# 1-Schematic.net
KiCad netlist of a schematic drawn in EasyEDA
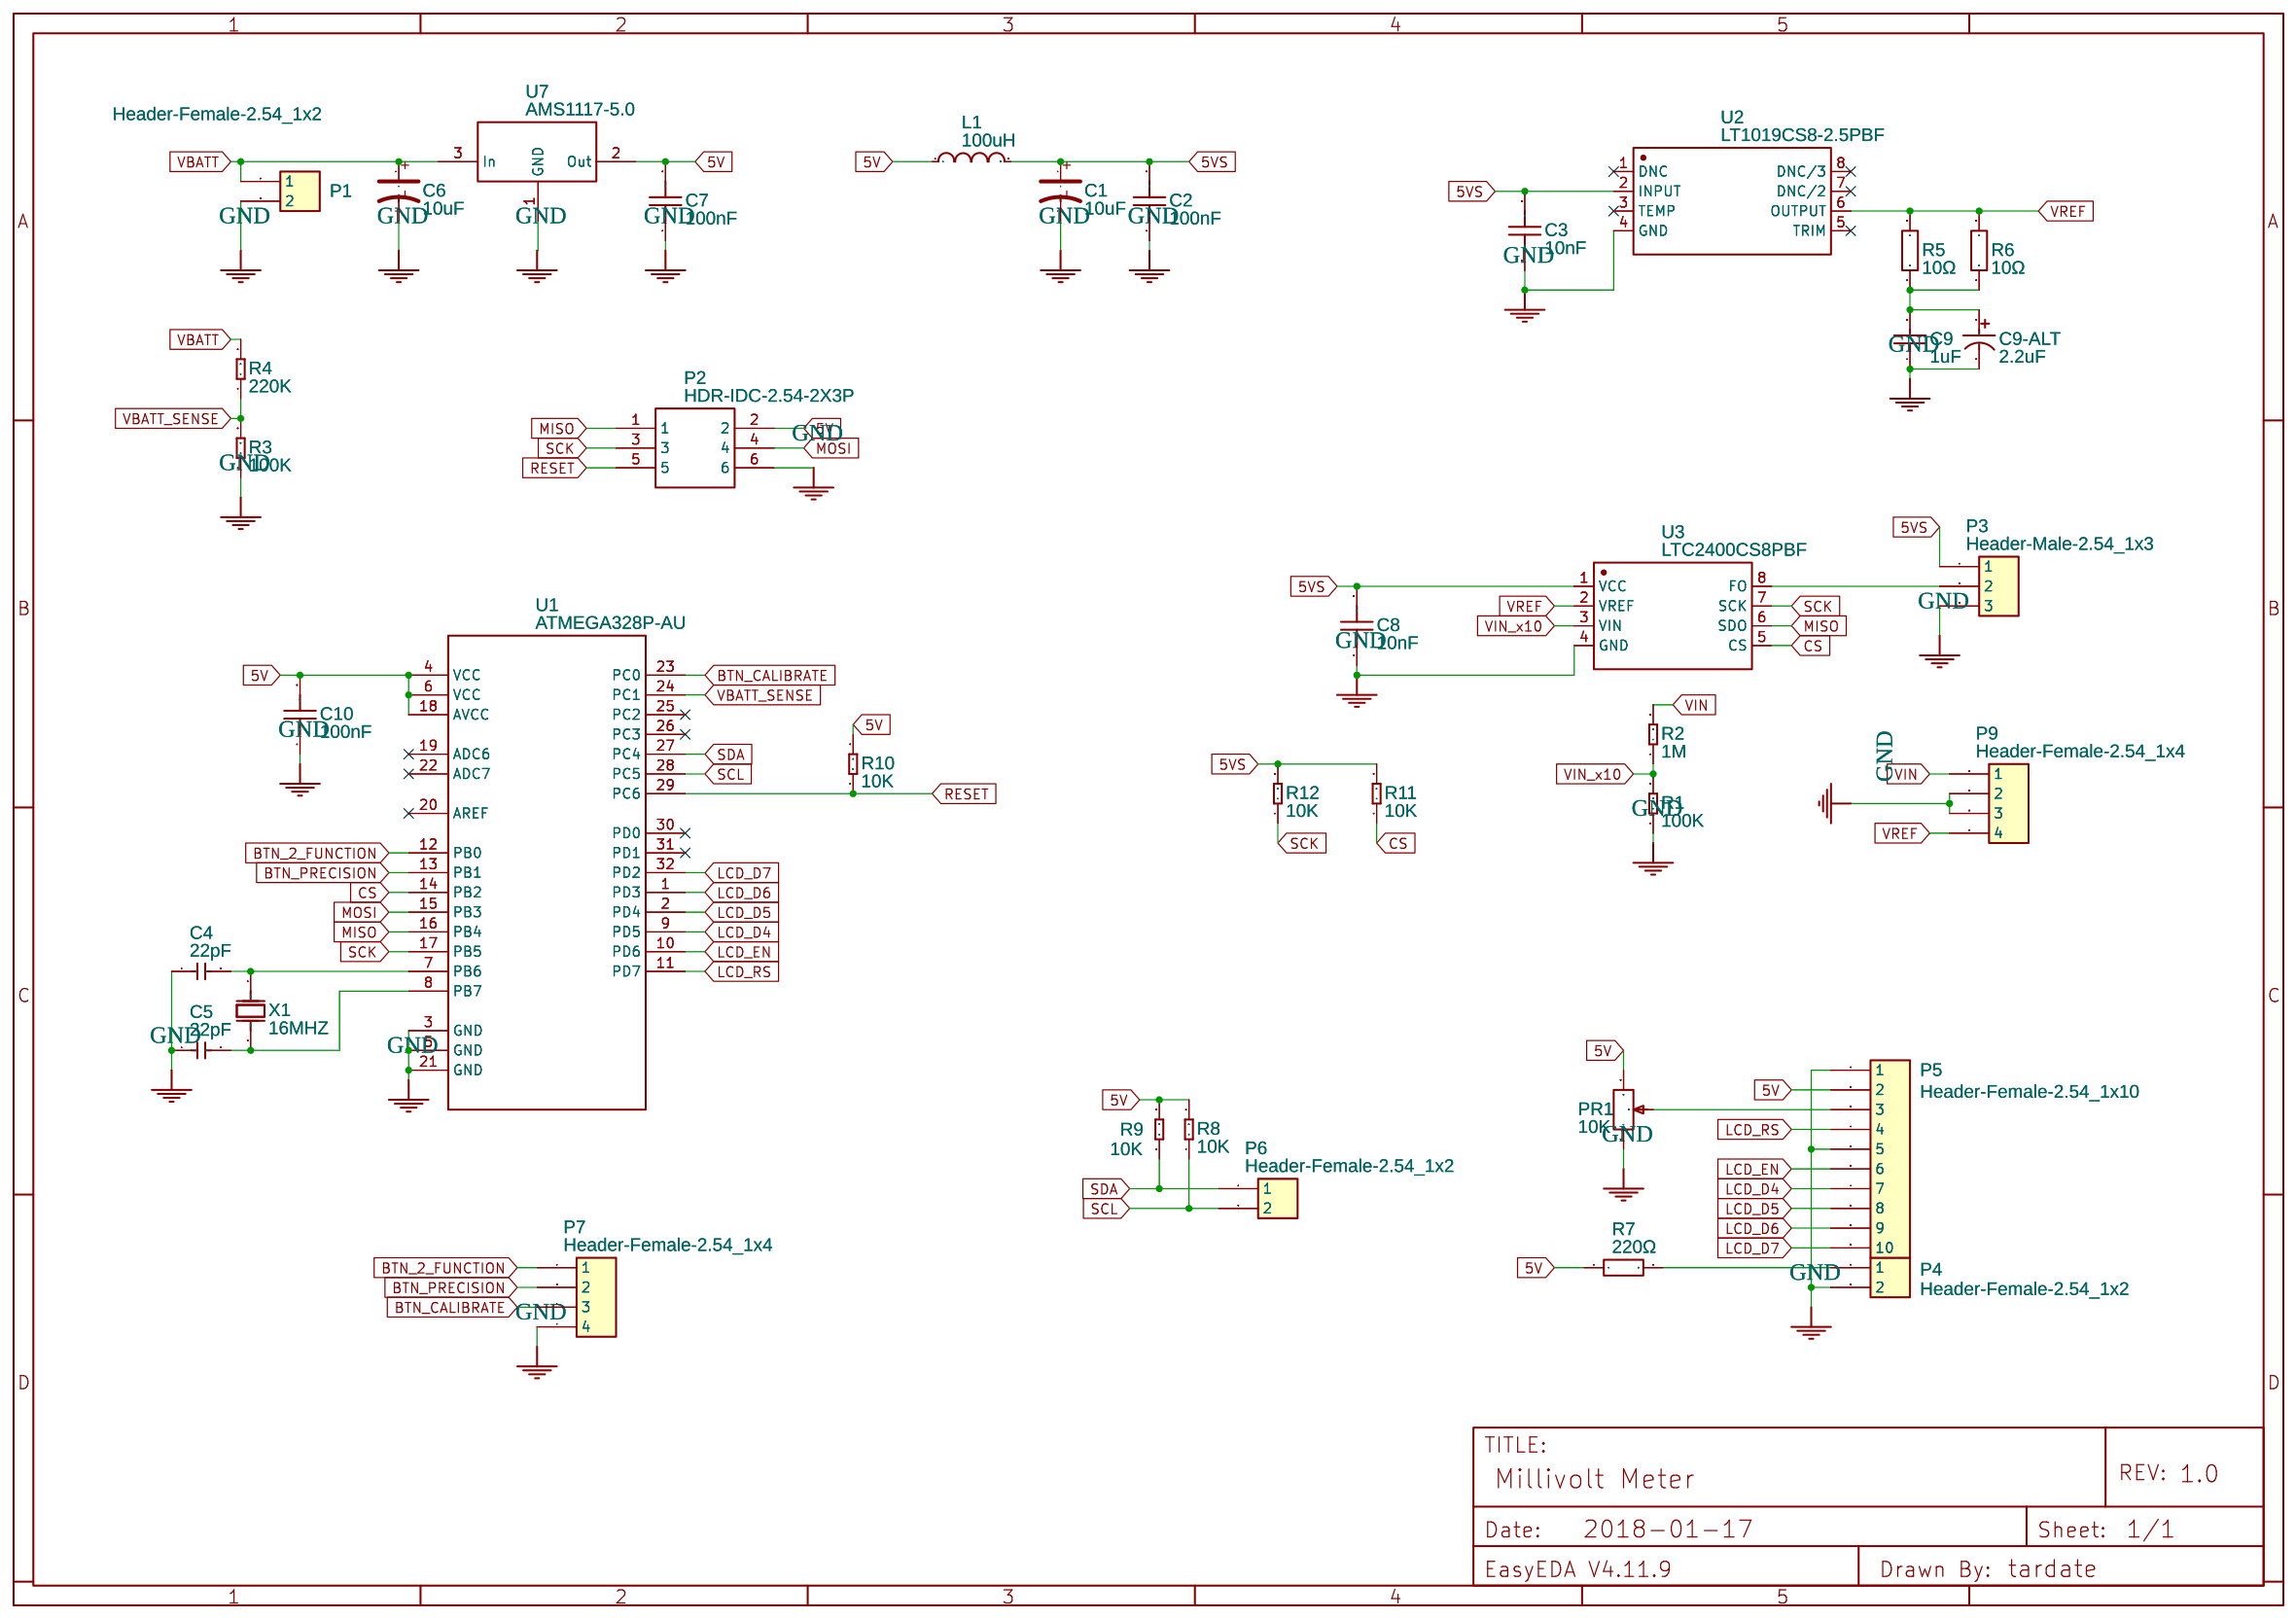
[diagram p0: schematic sheet]

(export (version "E")
  (design (tool "Eeschema 10.0.6"))
  (components
    (comp (ref "C1")
      (value "10uF")
      (fields (field (name "BOM_Manufacturer Part") "UWX1C100MCL1GB"))
      (libsource (lib "") (part "Unknown_530_90"))
    )
    (comp (ref "C2")
      (value "100nF")
      (fields (field (name "BOM_Manufacturer Part") "CC0805JRX7R9BB103"))
      (libsource (lib "") (part "Unknown_575_95"))
    )
    (comp (ref "C3")
      (value "10nF")
      (fields (field (name "BOM_Manufacturer Part") "CC0805KRX7R9BB103"))
      (libsource (lib "") (part "Unknown_765_110"))
    )
    (comp (ref "C4")
      (value "22pF")
      (fields (field (name "BOM_Manufacturer Part") "CC0805JRNPO9BN220"))
      (libsource (lib "") (part "Unknown_95_485"))
    )
    (comp (ref "C5")
      (value "22pF")
      (fields (field (name "BOM_Manufacturer Part") "CC0805JRNPO9BN220"))
      (libsource (lib "") (part "Unknown_95_525"))
    )
    (comp (ref "C6")
      (value "10uF")
      (fields (field (name "BOM_Manufacturer Part") "UWX1C100MCL1GB"))
      (libsource (lib "") (part "Unknown_195_90"))
    )
    (comp (ref "C7")
      (value "100nF")
      (fields (field (name "BOM_Manufacturer Part") "CC0805JRX7R9BB103"))
      (libsource (lib "") (part "Unknown_330_95"))
    )
    (comp (ref "C8")
      (value "10nF")
      (fields (field (name "BOM_Manufacturer Part") "CC0805KRX7R9BB103"))
      (libsource (lib "") (part "Unknown_680_310"))
    )
    (comp (ref "C9")
      (value "1uF")
      (fields (field (name "BOM_Manufacturer Part") "0805B105K500NT"))
      (libsource (lib "") (part "Unknown_960_165"))
    )
    (comp (ref "C9-ALT")
      (value "2.2uF")
      (fields (field (name "BOM_Manufacturer Part") "2.2uF 50V 5*11"))
      (libsource (lib "") (part "Unknown_995_165"))
    )
    (comp (ref "C10")
      (value "100nF")
      (fields (field (name "BOM_Manufacturer Part") "CC0805JRX7R9BB103"))
      (libsource (lib "") (part "Unknown_145_355"))
    )
    (comp (ref "L1")
      (value "100uH")
      (fields (field (name "BOM_Manufacturer Part") "MLF2012C101KT000"))
      (libsource (lib "") (part "Unknown_485_75"))
    )
    (comp (ref "P1") (value "Header-Female-2.54_1x2") (libsource (lib "") (part "Unknown_130_90")))
    (comp (ref "P2") (value "HDR-IDC-2.54-2X3P") (libsource (lib "") (part "Unknown_345_240")))
    (comp (ref "P3") (value "Header-Male-2.54_1x3") (libsource (lib "") (part "Unknown_990_290")))
    (comp (ref "P4") (value "Header-Female-2.54_1x2") (libsource (lib "") (part "Unknown_935_640")))
    (comp (ref "P5") (value "Header-Female-2.54_1x10") (libsource (lib "") (part "Unknown_935_580")))
    (comp (ref "P6") (value "Header-Female-2.54_1x2") (libsource (lib "") (part "Unknown_625_600")))
    (comp (ref "P7") (value "Header-Female-2.54_1x4") (libsource (lib "") (part "Unknown_280_650")))
    (comp (ref "P9") (value "Header-Female-2.54_1x4") (libsource (lib "") (part "Unknown_995_400")))
    (comp (ref "PR1")
      (value "10K")
      (fields (field (name "BOM_Manufacturer Part") "RM065-V1-103"))
      (libsource (lib "") (part "Unknown_820_555"))
    )
    (comp (ref "R1")
      (value "100K")
      (fields (field (name "BOM_Manufacturer Part") "RC0805FR-07100KL"))
      (libsource (lib "") (part "Unknown_830_400"))
    )
    (comp (ref "R2")
      (value "1M")
      (fields (field (name "BOM_Manufacturer Part") "RC0805JR-071ML"))
      (libsource (lib "") (part "Unknown_830_365"))
    )
    (comp (ref "R3")
      (value "100K")
      (fields (field (name "BOM_Manufacturer Part") "RC0805FR-07100KL"))
      (libsource (lib "") (part "Unknown_115_220"))
    )
    (comp (ref "R4")
      (value "220K")
      (fields (field (name "BOM_Manufacturer Part") "RC0603JR-07220KL"))
      (libsource (lib "") (part "Unknown_115_180"))
    )
    (comp (ref "R5")
      (value "10Ω")
      (fields (field (name "BOM_Manufacturer Part") "0805W8J0100T5E"))
      (libsource (lib "") (part "Unknown_960_120"))
    )
    (comp (ref "R6")
      (value "10Ω")
      (fields (field (name "BOM_Manufacturer Part") "0805W8J0100T5E"))
      (libsource (lib "") (part "Unknown_995_120"))
    )
    (comp (ref "R7")
      (value "220Ω")
      (fields (field (name "BOM_Manufacturer Part") "0805W8J0221T5E"))
      (libsource (lib "") (part "Unknown_815_635"))
    )
    (comp (ref "R8")
      (value "10K")
      (fields (field (name "BOM_Manufacturer Part") "RC0805FR-0710KL"))
      (libsource (lib "") (part "Unknown_595_565"))
    )
    (comp (ref "R9")
      (value "10K")
      (fields (field (name "BOM_Manufacturer Part") "RC0805FR-0710KL"))
      (libsource (lib "") (part "Unknown_580_565"))
    )
    (comp (ref "R10")
      (value "10K")
      (fields (field (name "BOM_Manufacturer Part") "RC0805FR-0710KL"))
      (libsource (lib "") (part "Unknown_425_380"))
    )
    (comp (ref "R11")
      (value "10K")
      (fields (field (name "BOM_Manufacturer Part") "RC0805FR-0710KL"))
      (libsource (lib "") (part "Unknown_690_395"))
    )
    (comp (ref "R12")
      (value "10K")
      (fields (field (name "BOM_Manufacturer Part") "RC0805FR-0710KL"))
      (libsource (lib "") (part "Unknown_640_395"))
    )
    (comp (ref "U1") (value "ATMEGA328P-AU") (libsource (lib "") (part "Unknown_270_425")))
    (comp (ref "U2")
      (value "LT1019CS8-2.5PBF")
      (fields (field (name "BOM_Manufacturer Part") "?"))
      (libsource (lib "") (part "Unknown_870_70"))
    )
    (comp (ref "U3")
      (value "LTC2400CS8PBF")
      (fields (field (name "BOM_Manufacturer Part") "?"))
      (libsource (lib "") (part "Unknown_840_280"))
    )
    (comp (ref "U7") (value "AMS1117-5.0") (libsource (lib "") (part "Unknown_265_75")))
    (comp (ref "X1")
      (value "16MHZ")
      (fields (field (name "BOM_Manufacturer Part") "X49SD16MSD2SC"))
      (libsource (lib "") (part "Unknown_120_505"))
    )
  )
  (nets
    (net (code "1") (name "5V") (class "Default")
      (node (ref "C10") (pin "2") (pinfunction "2_2") (pintype "unspecified"))
      (node (ref "C7") (pin "2") (pinfunction "2_2") (pintype "unspecified"))
      (node (ref "L1") (pin "1") (pinfunction "1_1") (pintype "unspecified"))
      (node (ref "P2") (pin "2") (pinfunction "2_2") (pintype "unspecified"))
      (node (ref "P5") (pin "2") (pinfunction "2_2") (pintype "input"))
      (node (ref "PR1") (pin "3") (pinfunction "3_3") (pintype "input"))
      (node (ref "R10") (pin "2") (pinfunction "2_2") (pintype "unspecified"))
      (node (ref "R7") (pin "1") (pinfunction "1_1") (pintype "input"))
      (node (ref "R8") (pin "2") (pinfunction "2_2") (pintype "unspecified"))
      (node (ref "R9") (pin "2") (pinfunction "2_2") (pintype "unspecified"))
      (node (ref "U1") (pin "18") (pinfunction "AVCC_18") (pintype "passive"))
      (node (ref "U1") (pin "4") (pinfunction "VCC_4") (pintype "passive"))
      (node (ref "U1") (pin "6") (pinfunction "VCC_6") (pintype "passive"))
      (node (ref "U7") (pin "2") (pinfunction "Out_2") (pintype "unspecified"))
    )
    (net (code "2") (name "5VS") (class "Default")
      (node (ref "C1") (pin "+") (pinfunction "+_+") (pintype "unspecified"))
      (node (ref "C2") (pin "2") (pinfunction "2_2") (pintype "unspecified"))
      (node (ref "C3") (pin "2") (pinfunction "2_2") (pintype "unspecified"))
      (node (ref "C8") (pin "2") (pinfunction "2_2") (pintype "unspecified"))
      (node (ref "L1") (pin "2") (pinfunction "2_2") (pintype "unspecified"))
      (node (ref "P3") (pin "1") (pinfunction "1_1") (pintype "input"))
      (node (ref "R11") (pin "2") (pinfunction "2_2") (pintype "unspecified"))
      (node (ref "R12") (pin "2") (pinfunction "2_2") (pintype "unspecified"))
      (node (ref "U2") (pin "2") (pinfunction "INPUT_2") (pintype "unspecified"))
      (node (ref "U3") (pin "1") (pinfunction "VCC_1") (pintype "unspecified"))
    )
    (net (code "3") (name "BTN_2_FUNCTION") (class "Default")
      (node (ref "P7") (pin "1") (pinfunction "1_1") (pintype "input"))
      (node (ref "U1") (pin "12") (pinfunction "PB0_12") (pintype "unspecified"))
    )
    (net (code "4") (name "BTN_CALIBRATE") (class "Default")
      (node (ref "P7") (pin "3") (pinfunction "3_3") (pintype "input"))
      (node (ref "U1") (pin "23") (pinfunction "PC0_23") (pintype "unspecified"))
    )
    (net (code "5") (name "BTN_PRECISION") (class "Default")
      (node (ref "P7") (pin "2") (pinfunction "2_2") (pintype "input"))
      (node (ref "U1") (pin "13") (pinfunction "PB1_13") (pintype "unspecified"))
    )
    (net (code "6") (name "CS") (class "Default")
      (node (ref "R11") (pin "1") (pinfunction "1_1") (pintype "unspecified"))
      (node (ref "U1") (pin "14") (pinfunction "PB2_14") (pintype "unspecified"))
      (node (ref "U3") (pin "5") (pinfunction "CS_5") (pintype "unspecified"))
    )
    (net (code "7") (name "GND") (class "Default")
      (node (ref "C1") (pin "-") (pinfunction "-_-") (pintype "unspecified"))
      (node (ref "C10") (pin "1") (pinfunction "1_1") (pintype "unspecified"))
      (node (ref "C2") (pin "1") (pinfunction "1_1") (pintype "unspecified"))
      (node (ref "C3") (pin "1") (pinfunction "1_1") (pintype "unspecified"))
      (node (ref "C4") (pin "1") (pinfunction "1_1") (pintype "unspecified"))
      (node (ref "C5") (pin "1") (pinfunction "1_1") (pintype "unspecified"))
      (node (ref "C6") (pin "-") (pinfunction "-_-") (pintype "unspecified"))
      (node (ref "C7") (pin "1") (pinfunction "1_1") (pintype "unspecified"))
      (node (ref "C8") (pin "1") (pinfunction "1_1") (pintype "unspecified"))
      (node (ref "C9") (pin "1") (pinfunction "1_1") (pintype "input"))
      (node (ref "C9-ALT") (pin "2") (pinfunction "2_2") (pintype "input"))
      (node (ref "P1") (pin "2") (pinfunction "2_2") (pintype "input"))
      (node (ref "P2") (pin "6") (pinfunction "6_6") (pintype "unspecified"))
      (node (ref "P3") (pin "3") (pinfunction "3_3") (pintype "input"))
      (node (ref "P4") (pin "2") (pinfunction "2_2") (pintype "input"))
      (node (ref "P5") (pin "1") (pinfunction "1_1") (pintype "input"))
      (node (ref "P5") (pin "5") (pinfunction "5_5") (pintype "input"))
      (node (ref "P7") (pin "4") (pinfunction "4_4") (pintype "input"))
      (node (ref "P9") (pin "2") (pinfunction "2_2") (pintype "input"))
      (node (ref "P9") (pin "3") (pinfunction "3_3") (pintype "input"))
      (node (ref "PR1") (pin "1") (pinfunction "1_1") (pintype "input"))
      (node (ref "R1") (pin "1") (pinfunction "1_1") (pintype "unspecified"))
      (node (ref "R3") (pin "1") (pinfunction "1_1") (pintype "unspecified"))
      (node (ref "U1") (pin "21") (pinfunction "GND_21") (pintype "unspecified"))
      (node (ref "U1") (pin "3") (pinfunction "GND_3") (pintype "unspecified"))
      (node (ref "U1") (pin "5") (pinfunction "GND_5") (pintype "unspecified"))
      (node (ref "U2") (pin "4") (pinfunction "GND_4") (pintype "unspecified"))
      (node (ref "U3") (pin "4") (pinfunction "GND_4") (pintype "unspecified"))
      (node (ref "U7") (pin "1") (pinfunction "GND_1") (pintype "unspecified"))
    )
    (net (code "8") (name "LCD_D4") (class "Default")
      (node (ref "P5") (pin "7") (pinfunction "7_7") (pintype "input"))
      (node (ref "U1") (pin "9") (pinfunction "PD5_9") (pintype "unspecified"))
    )
    (net (code "9") (name "LCD_D5") (class "Default")
      (node (ref "P5") (pin "8") (pinfunction "8_8") (pintype "input"))
      (node (ref "U1") (pin "2") (pinfunction "PD4_2") (pintype "unspecified"))
    )
    (net (code "10") (name "LCD_D6") (class "Default")
      (node (ref "P5") (pin "9") (pinfunction "9_9") (pintype "input"))
      (node (ref "U1") (pin "1") (pinfunction "PD3_1") (pintype "unspecified"))
    )
    (net (code "11") (name "LCD_D7") (class "Default")
      (node (ref "P5") (pin "10") (pinfunction "10_10") (pintype "input"))
      (node (ref "U1") (pin "32") (pinfunction "PD2_32") (pintype "unspecified"))
    )
    (net (code "12") (name "LCD_EN") (class "Default")
      (node (ref "P5") (pin "6") (pinfunction "6_6") (pintype "input"))
      (node (ref "U1") (pin "10") (pinfunction "PD6_10") (pintype "unspecified"))
    )
    (net (code "13") (name "LCD_RS") (class "Default")
      (node (ref "P5") (pin "4") (pinfunction "4_4") (pintype "input"))
      (node (ref "U1") (pin "11") (pinfunction "PD7_11") (pintype "unspecified"))
    )
    (net (code "14") (name "MISO") (class "Default")
      (node (ref "P2") (pin "1") (pinfunction "1_1") (pintype "unspecified"))
      (node (ref "U1") (pin "16") (pinfunction "PB4_16") (pintype "unspecified"))
      (node (ref "U3") (pin "6") (pinfunction "SDO_6") (pintype "unspecified"))
    )
    (net (code "15") (name "MOSI") (class "Default")
      (node (ref "P2") (pin "4") (pinfunction "4_4") (pintype "unspecified"))
      (node (ref "U1") (pin "15") (pinfunction "PB3_15") (pintype "unspecified"))
    )
    (net (code "16") (name "Net-(C9-ALT-Pad1)") (class "Default")
      (node (ref "C9") (pin "2") (pinfunction "2_2") (pintype "input"))
      (node (ref "C9-ALT") (pin "1") (pinfunction "1_1") (pintype "input"))
      (node (ref "R5") (pin "1") (pinfunction "1_1") (pintype "input"))
      (node (ref "R6") (pin "1") (pinfunction "1_1") (pintype "input"))
    )
    (net (code "17") (name "Net-(P4-Pad1)") (class "Default")
      (node (ref "P4") (pin "1") (pinfunction "1_1") (pintype "input"))
      (node (ref "R7") (pin "2") (pinfunction "2_2") (pintype "input"))
    )
    (net (code "18") (name "Net-(P5-Pad3)") (class "Default")
      (node (ref "P5") (pin "3") (pinfunction "3_3") (pintype "input"))
      (node (ref "PR1") (pin "2") (pinfunction "2_2") (pintype "input"))
    )
    (net (code "19") (name "Net-(U1-PB6)") (class "Default")
      (node (ref "C4") (pin "2") (pinfunction "2_2") (pintype "unspecified"))
      (node (ref "U1") (pin "7") (pinfunction "PB6_7") (pintype "unspecified"))
      (node (ref "X1") (pin "1") (pinfunction "OSC1_1") (pintype "input"))
    )
    (net (code "20") (name "Net-(U1-PB7)") (class "Default")
      (node (ref "C5") (pin "2") (pinfunction "2_2") (pintype "unspecified"))
      (node (ref "U1") (pin "8") (pinfunction "PB7_8") (pintype "unspecified"))
      (node (ref "X1") (pin "2") (pinfunction "OSC2_2") (pintype "input"))
    )
    (net (code "21") (name "Net-(U3-FO)") (class "Default")
      (node (ref "P3") (pin "2") (pinfunction "2_2") (pintype "input"))
      (node (ref "U3") (pin "8") (pinfunction "FO_8") (pintype "unspecified"))
    )
    (net (code "22") (name "RESET") (class "Default")
      (node (ref "P2") (pin "5") (pinfunction "5_5") (pintype "unspecified"))
      (node (ref "R10") (pin "1") (pinfunction "1_1") (pintype "unspecified"))
      (node (ref "U1") (pin "29") (pinfunction "PC6_29") (pintype "unspecified"))
    )
    (net (code "23") (name "SCK") (class "Default")
      (node (ref "P2") (pin "3") (pinfunction "3_3") (pintype "unspecified"))
      (node (ref "R12") (pin "1") (pinfunction "1_1") (pintype "unspecified"))
      (node (ref "U1") (pin "17") (pinfunction "PB5_17") (pintype "unspecified"))
      (node (ref "U3") (pin "7") (pinfunction "SCK_7") (pintype "unspecified"))
    )
    (net (code "24") (name "SCL") (class "Default")
      (node (ref "P6") (pin "2") (pinfunction "2_2") (pintype "input"))
      (node (ref "R8") (pin "1") (pinfunction "1_1") (pintype "unspecified"))
      (node (ref "U1") (pin "28") (pinfunction "PC5_28") (pintype "unspecified"))
    )
    (net (code "25") (name "SDA") (class "Default")
      (node (ref "P6") (pin "1") (pinfunction "1_1") (pintype "input"))
      (node (ref "R9") (pin "1") (pinfunction "1_1") (pintype "unspecified"))
      (node (ref "U1") (pin "27") (pinfunction "PC4_27") (pintype "unspecified"))
    )
    (net (code "26") (name "VBATT") (class "Default")
      (node (ref "C6") (pin "+") (pinfunction "+_+") (pintype "unspecified"))
      (node (ref "P1") (pin "1") (pinfunction "1_1") (pintype "input"))
      (node (ref "R4") (pin "2") (pinfunction "2_2") (pintype "unspecified"))
      (node (ref "U7") (pin "3") (pinfunction "In_3") (pintype "unspecified"))
    )
    (net (code "27") (name "VBATT_SENSE") (class "Default")
      (node (ref "R3") (pin "2") (pinfunction "2_2") (pintype "unspecified"))
      (node (ref "R4") (pin "1") (pinfunction "1_1") (pintype "unspecified"))
      (node (ref "U1") (pin "24") (pinfunction "PC1_24") (pintype "unspecified"))
    )
    (net (code "28") (name "VIN") (class "Default")
      (node (ref "P9") (pin "1") (pinfunction "1_1") (pintype "input"))
      (node (ref "R2") (pin "2") (pinfunction "2_2") (pintype "unspecified"))
    )
    (net (code "29") (name "VIN_x10") (class "Default")
      (node (ref "R1") (pin "2") (pinfunction "2_2") (pintype "unspecified"))
      (node (ref "R2") (pin "1") (pinfunction "1_1") (pintype "unspecified"))
      (node (ref "U3") (pin "3") (pinfunction "VIN_3") (pintype "unspecified"))
    )
    (net (code "30") (name "VREF") (class "Default")
      (node (ref "P9") (pin "4") (pinfunction "4_4") (pintype "input"))
      (node (ref "R5") (pin "2") (pinfunction "2_2") (pintype "input"))
      (node (ref "R6") (pin "2") (pinfunction "2_2") (pintype "input"))
      (node (ref "U2") (pin "6") (pinfunction "OUTPUT_6") (pintype "unspecified"))
      (node (ref "U3") (pin "2") (pinfunction "VREF_2") (pintype "unspecified"))
    )
    (net (code "31") (name "unconnected-(U1-ADC6-Pad19)") (class "Default")
      (node (ref "U1") (pin "19") (pinfunction "ADC6_19") (pintype "input+no_connect"))
    )
    (net (code "32") (name "unconnected-(U1-ADC7-Pad22)") (class "Default")
      (node (ref "U1") (pin "22") (pinfunction "ADC7_22") (pintype "input+no_connect"))
    )
    (net (code "33") (name "unconnected-(U1-AREF-Pad20)") (class "Default")
      (node (ref "U1") (pin "20") (pinfunction "AREF_20") (pintype "input+no_connect"))
    )
    (net (code "34") (name "unconnected-(U1-PC2-Pad25)") (class "Default")
      (node (ref "U1") (pin "25") (pinfunction "PC2_25") (pintype "unspecified+no_connect"))
    )
    (net (code "35") (name "unconnected-(U1-PC3-Pad26)") (class "Default")
      (node (ref "U1") (pin "26") (pinfunction "PC3_26") (pintype "unspecified+no_connect"))
    )
    (net (code "36") (name "unconnected-(U1-PD0-Pad30)") (class "Default")
      (node (ref "U1") (pin "30") (pinfunction "PD0_30") (pintype "unspecified+no_connect"))
    )
    (net (code "37") (name "unconnected-(U1-PD1-Pad31)") (class "Default")
      (node (ref "U1") (pin "31") (pinfunction "PD1_31") (pintype "unspecified+no_connect"))
    )
    (net (code "38") (name "unconnected-(U2-DNC-Pad1)") (class "Default")
      (node (ref "U2") (pin "1") (pinfunction "DNC_1") (pintype "unspecified+no_connect"))
    )
    (net (code "39") (name "unconnected-(U2-DNC{slash}2-Pad7)") (class "Default")
      (node (ref "U2") (pin "7") (pinfunction "DNC/2_7") (pintype "unspecified+no_connect"))
    )
    (net (code "40") (name "unconnected-(U2-DNC{slash}3-Pad8)") (class "Default")
      (node (ref "U2") (pin "8") (pinfunction "DNC/3_8") (pintype "unspecified+no_connect"))
    )
    (net (code "41") (name "unconnected-(U2-TEMP-Pad3)") (class "Default")
      (node (ref "U2") (pin "3") (pinfunction "TEMP_3") (pintype "unspecified+no_connect"))
    )
    (net (code "42") (name "unconnected-(U2-TRIM-Pad5)") (class "Default")
      (node (ref "U2") (pin "5") (pinfunction "TRIM_5") (pintype "unspecified+no_connect"))
    )
  )
)
